# MC2.net
KiCad netlist of a schematic drawn in Altium Designer
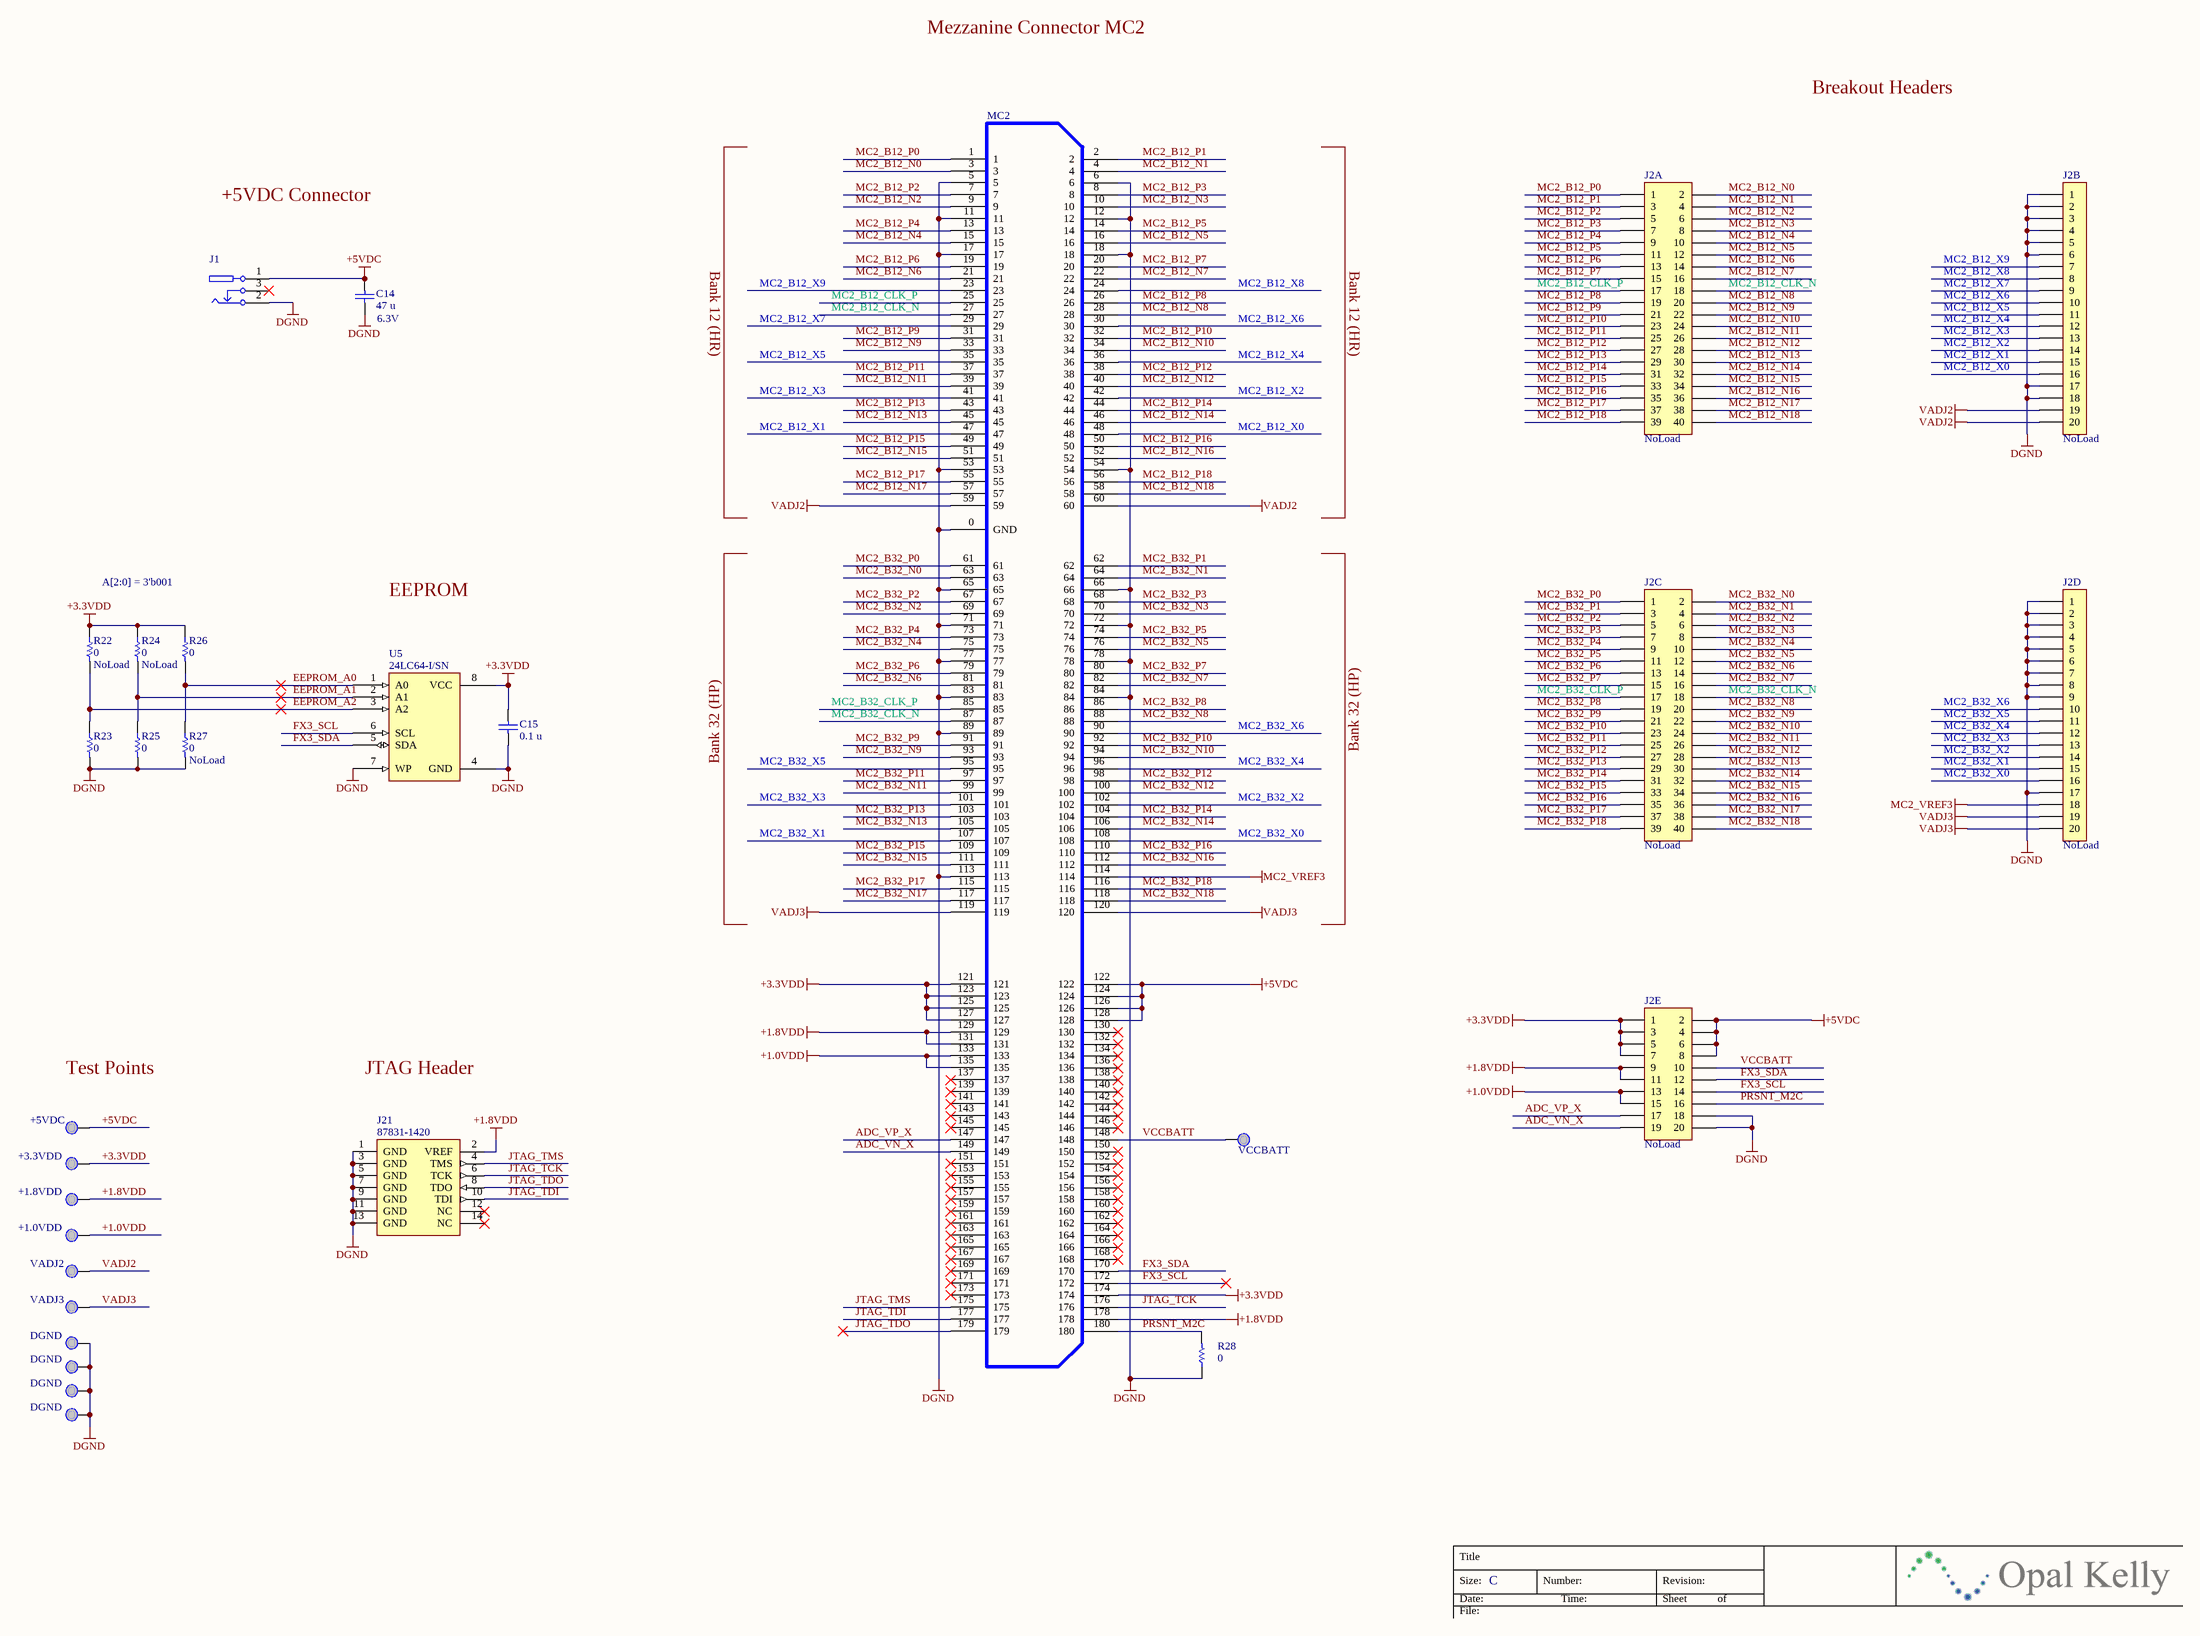
[diagram p0: MC2.SchDoc]

(export (version "E")
  (design (tool "Eeschema 10.0.6"))
  (components
    (comp (ref "C14")
      (value "47 u")
      (footprint "CAPC3216N")
      (description "Ceramic Capacitor")
      (fields
        (field (name "MANUFACTURER") "Taiyo Yuden")
        (field (name "PARTNUMBER") "000570")
        (field (name "VOLTAGERATING") "6.3V")
      )
      (libsource (lib "Aligni") (part "Capacitor"))
    )
    (comp (ref "C15")
      (value "0.1 u")
      (footprint "CAPC1005N")
      (description "Ceramic capacitor")
      (fields (field (name "MANUFACTURER") "Kemet") (field (name "PARTNUMBER") "000070"))
      (libsource (lib "Aligni") (part "Capacitor"))
    )
    (comp (ref "J1")
      (value "PJ-102AH")
      (footprint "CUI-PJ102A")
      (description "DC power connector - high current")
      (fields (field (name "MANUFACTURER") "CUI Inc.") (field (name "PARTNUMBER") "000356"))
      (libsource (lib "Aligni") (part "DCPOWER"))
    )
    (comp (ref "J2A")
      (value "0877584016")
      (footprint "HDR2X20-2MM")
      (description "2mm header, 20x2, thru-hole")
      (fields
        (field (name "MANUFACTURER") "Molex")
        (field (name "PARTNUMBER") "000583")
        (field (name "NOLOAD") "NoLoad")
      )
      (libsource (lib "Aligni") (part "Header 20X2"))
    )
    (comp (ref "J2B")
      (value "Header, 20-Pin, Single Row")
      (footprint "HDR1X20-2MM")
      (description "2mm header, 20x1, thru-hole")
      (fields
        (field (name "PARTNUMBER") "001334")
        (field (name "MANUFACTURER") "3M")
        (field (name "NOLOAD") "NoLoad")
      )
      (libsource (lib "Aligni") (part "Header 1X20"))
    )
    (comp (ref "J2C")
      (value "0877584016")
      (footprint "HDR2X20-2MM")
      (description "2mm header, 20x2, thru-hole")
      (fields
        (field (name "MANUFACTURER") "Molex")
        (field (name "PARTNUMBER") "000583")
        (field (name "NOLOAD") "NoLoad")
      )
      (libsource (lib "Aligni") (part "Header 20X2"))
    )
    (comp (ref "J2D")
      (value "Header, 20-Pin, Single Row")
      (footprint "HDR1X20-2MM")
      (description "2mm header, 20x1, thru-hole")
      (fields
        (field (name "PARTNUMBER") "001334")
        (field (name "MANUFACTURER") "3M")
        (field (name "NOLOAD") "NoLoad")
      )
      (libsource (lib "Aligni") (part "Header 1X20"))
    )
    (comp (ref "J2E")
      (value "0877582016")
      (footprint "HDR2X10-2MM")
      (description "2mm header, 10x2, thru-hole")
      (fields
        (field (name "MANUFACTURER") "Molex")
        (field (name "PARTNUMBER") "001338")
        (field (name "NOLOAD") "NoLoad")
      )
      (libsource (lib "Aligni") (part "Header 10X2"))
    )
    (comp (ref "J21")
      (value "87831-1420")
      (footprint "HDR2X7-2MM")
      (description "2mm header, shrouded")
      (fields (field (name "MANUFACTURER") "Molex") (field (name "PARTNUMBER") "000541"))
      (libsource (lib "Aligni") (part "JTAGXLNX"))
    )
    (comp (ref "MC2")
      (value "QTH-090-01-F-D-A")
      (footprint "QTH-090-01-X-D")
      (description "0.5mm hi-speed, high-density header (Female)")
      (fields (field (name "MANUFACTURER") "Samtec") (field (name "PARTNUMBER") "000876"))
      (libsource (lib "Aligni") (part "QTH-090"))
    )
    (comp (ref "R22")
      (value "0")
      (footprint "RESC1005N")
      (description "Thick-film resistor")
      (fields
        (field (name "MANUFACTURER") "Vishay")
        (field (name "PARTNUMBER") "000755")
        (field (name "NOLOAD") "NoLoad")
      )
      (libsource (lib "Aligni") (part "Resistor"))
    )
    (comp (ref "R23")
      (value "0")
      (footprint "RESC1005N")
      (description "Thick-film resistor")
      (fields (field (name "MANUFACTURER") "Vishay") (field (name "PARTNUMBER") "000755"))
      (libsource (lib "Aligni") (part "Resistor"))
    )
    (comp (ref "R24")
      (value "0")
      (footprint "RESC1005N")
      (description "Thick-film resistor")
      (fields
        (field (name "MANUFACTURER") "Vishay")
        (field (name "PARTNUMBER") "000755")
        (field (name "NOLOAD") "NoLoad")
      )
      (libsource (lib "Aligni") (part "Resistor"))
    )
    (comp (ref "R25")
      (value "0")
      (footprint "RESC1005N")
      (description "Thick-film resistor")
      (fields (field (name "MANUFACTURER") "Vishay") (field (name "PARTNUMBER") "000755"))
      (libsource (lib "Aligni") (part "Resistor"))
    )
    (comp (ref "R26")
      (value "0")
      (footprint "RESC1005N")
      (description "Thick-film resistor")
      (fields (field (name "MANUFACTURER") "Vishay") (field (name "PARTNUMBER") "000755"))
      (libsource (lib "Aligni") (part "Resistor"))
    )
    (comp (ref "R27")
      (value "0")
      (footprint "RESC1005N")
      (description "Thick-film resistor")
      (fields
        (field (name "MANUFACTURER") "Vishay")
        (field (name "PARTNUMBER") "000755")
        (field (name "NOLOAD") "NoLoad")
      )
      (libsource (lib "Aligni") (part "Resistor"))
    )
    (comp (ref "R28")
      (value "0")
      (footprint "RESC1608N")
      (description "Zero-ohm resistor")
      (fields (field (name "MANUFACTURER") "Vishay") (field (name "PARTNUMBER") "000411"))
      (libsource (lib "Aligni") (part "Resistor"))
    )
    (comp (ref "TP2")
      (value "+5VDC")
      (footprint "TP_MED")
      (description "Testpoint")
      (fields (field (name "MANUFACTURER") "Keystone Electronics") (field (name "PARTNUMBER") "000265"))
      (libsource (lib "Aligni") (part "TESTPOINT"))
    )
    (comp (ref "TP3")
      (value "+3.3VDD")
      (footprint "TP_MED")
      (description "Testpoint")
      (fields (field (name "MANUFACTURER") "Keystone Electronics") (field (name "PARTNUMBER") "000265"))
      (libsource (lib "Aligni") (part "TESTPOINT"))
    )
    (comp (ref "TP4")
      (value "+1.8VDD")
      (footprint "TP_MED")
      (description "Testpoint")
      (fields (field (name "MANUFACTURER") "Keystone Electronics") (field (name "PARTNUMBER") "000265"))
      (libsource (lib "Aligni") (part "TESTPOINT"))
    )
    (comp (ref "TP5")
      (value "+1.0VDD")
      (footprint "TP_MED")
      (description "Testpoint")
      (fields (field (name "MANUFACTURER") "Keystone Electronics") (field (name "PARTNUMBER") "000265"))
      (libsource (lib "Aligni") (part "TESTPOINT"))
    )
    (comp (ref "TP6")
      (value "VCCBATT")
      (footprint "TP_MED")
      (description "Testpoint")
      (fields (field (name "MANUFACTURER") "Keystone Electronics") (field (name "PARTNUMBER") "000265"))
      (libsource (lib "Aligni") (part "TESTPOINT"))
    )
    (comp (ref "TP9")
      (value "VADJ2")
      (footprint "TP_MED")
      (description "Testpoint")
      (fields (field (name "MANUFACTURER") "Keystone Electronics") (field (name "PARTNUMBER") "000265"))
      (libsource (lib "Aligni") (part "TESTPOINT"))
    )
    (comp (ref "TP10")
      (value "VADJ3")
      (footprint "TP_MED")
      (description "Testpoint")
      (fields (field (name "MANUFACTURER") "Keystone Electronics") (field (name "PARTNUMBER") "000265"))
      (libsource (lib "Aligni") (part "TESTPOINT"))
    )
    (comp (ref "TP11")
      (value "DGND")
      (footprint "TP_MED")
      (description "Testpoint")
      (fields (field (name "MANUFACTURER") "Keystone Electronics") (field (name "PARTNUMBER") "000265"))
      (libsource (lib "Aligni") (part "TESTPOINT"))
    )
    (comp (ref "TP12")
      (value "DGND")
      (footprint "TP_MED")
      (description "Testpoint")
      (fields (field (name "MANUFACTURER") "Keystone Electronics") (field (name "PARTNUMBER") "000265"))
      (libsource (lib "Aligni") (part "TESTPOINT"))
    )
    (comp (ref "TP13")
      (value "DGND")
      (footprint "TP_MED")
      (description "Testpoint")
      (fields (field (name "MANUFACTURER") "Keystone Electronics") (field (name "PARTNUMBER") "000265"))
      (libsource (lib "Aligni") (part "TESTPOINT"))
    )
    (comp (ref "TP14")
      (value "DGND")
      (footprint "TP_MED")
      (description "Testpoint")
      (fields (field (name "MANUFACTURER") "Keystone Electronics") (field (name "PARTNUMBER") "000265"))
      (libsource (lib "Aligni") (part "TESTPOINT"))
    )
    (comp (ref "U5")
      (value "24LC64-I/SN")
      (footprint "SO-G8")
      (description "EEPROM")
      (fields (field (name "MANUFACTURER") "Microchip") (field (name "PARTNUMBER") "000004"))
      (libsource (lib "Aligni") (part "24LCXX"))
    )
  )
  (nets
    (net (code "1") (name "+1.0VDD") (class "Default")
      (node (ref "J2E") (pin "13") (pinfunction "13_13") (pintype "passive"))
      (node (ref "J2E") (pin "15") (pinfunction "15_15") (pintype "passive"))
      (node (ref "MC2") (pin "133") (pinfunction "133_133") (pintype "passive"))
      (node (ref "MC2") (pin "135") (pinfunction "135_135") (pintype "passive"))
      (node (ref "TP5") (pin "1") (pinfunction "PIN_1") (pintype "passive"))
    )
    (net (code "2") (name "+1.8VDD") (class "Default")
      (node (ref "J21") (pin "2") (pinfunction "VREF_2") (pintype "power_in"))
      (node (ref "J2E") (pin "11") (pinfunction "11_11") (pintype "passive"))
      (node (ref "J2E") (pin "9") (pinfunction "9_9") (pintype "passive"))
      (node (ref "MC2") (pin "129") (pinfunction "129_129") (pintype "passive"))
      (node (ref "MC2") (pin "131") (pinfunction "131_131") (pintype "passive"))
      (node (ref "MC2") (pin "178") (pinfunction "178_178") (pintype "passive"))
      (node (ref "TP4") (pin "1") (pinfunction "PIN_1") (pintype "passive"))
    )
    (net (code "3") (name "+3.3VDD") (class "Default")
      (node (ref "C15") (pin "1") (pinfunction "1_1") (pintype "passive"))
      (node (ref "J2E") (pin "1") (pinfunction "1_1") (pintype "passive"))
      (node (ref "J2E") (pin "3") (pinfunction "3_3") (pintype "passive"))
      (node (ref "J2E") (pin "5") (pinfunction "5_5") (pintype "passive"))
      (node (ref "J2E") (pin "7") (pinfunction "7_7") (pintype "passive"))
      (node (ref "MC2") (pin "121") (pinfunction "121_121") (pintype "passive"))
      (node (ref "MC2") (pin "123") (pinfunction "123_123") (pintype "passive"))
      (node (ref "MC2") (pin "125") (pinfunction "125_125") (pintype "passive"))
      (node (ref "MC2") (pin "127") (pinfunction "127_127") (pintype "passive"))
      (node (ref "MC2") (pin "174") (pinfunction "174_174") (pintype "passive"))
      (node (ref "R22") (pin "1") (pinfunction "1_1") (pintype "passive"))
      (node (ref "R24") (pin "1") (pinfunction "1_1") (pintype "passive"))
      (node (ref "R26") (pin "1") (pinfunction "1_1") (pintype "passive"))
      (node (ref "TP3") (pin "1") (pinfunction "PIN_1") (pintype "passive"))
      (node (ref "U5") (pin "8") (pinfunction "VCC_8") (pintype "power_in"))
    )
    (net (code "4") (name "+5VDC") (class "Default")
      (node (ref "C14") (pin "1") (pinfunction "1_1") (pintype "passive"))
      (node (ref "J1") (pin "1") (pinfunction "1_1") (pintype "passive"))
      (node (ref "J2E") (pin "2") (pinfunction "2_2") (pintype "passive"))
      (node (ref "J2E") (pin "4") (pinfunction "4_4") (pintype "passive"))
      (node (ref "J2E") (pin "6") (pinfunction "6_6") (pintype "passive"))
      (node (ref "J2E") (pin "8") (pinfunction "8_8") (pintype "passive"))
      (node (ref "MC2") (pin "122") (pinfunction "122_122") (pintype "passive"))
      (node (ref "MC2") (pin "124") (pinfunction "124_124") (pintype "passive"))
      (node (ref "MC2") (pin "126") (pinfunction "126_126") (pintype "passive"))
      (node (ref "MC2") (pin "128") (pinfunction "128_128") (pintype "passive"))
      (node (ref "TP2") (pin "1") (pinfunction "PIN_1") (pintype "passive"))
    )
    (net (code "5") (name "/ADC_VN_X") (class "Default")
      (node (ref "J2E") (pin "19") (pinfunction "19_19") (pintype "passive"))
      (node (ref "MC2") (pin "149") (pinfunction "149_149") (pintype "passive"))
    )
    (net (code "6") (name "/ADC_VP_X") (class "Default")
      (node (ref "J2E") (pin "17") (pinfunction "17_17") (pintype "passive"))
      (node (ref "MC2") (pin "147") (pinfunction "147_147") (pintype "passive"))
    )
    (net (code "7") (name "/EEPROM_A0") (class "Default")
      (node (ref "R26") (pin "2") (pinfunction "2_2") (pintype "passive"))
      (node (ref "R27") (pin "1") (pinfunction "1_1") (pintype "passive"))
      (node (ref "U5") (pin "1") (pinfunction "A0_1") (pintype "input"))
    )
    (net (code "8") (name "/EEPROM_A1") (class "Default")
      (node (ref "R24") (pin "2") (pinfunction "2_2") (pintype "passive"))
      (node (ref "R25") (pin "1") (pinfunction "1_1") (pintype "passive"))
      (node (ref "U5") (pin "2") (pinfunction "A1_2") (pintype "input"))
    )
    (net (code "9") (name "/EEPROM_A2") (class "Default")
      (node (ref "R22") (pin "2") (pinfunction "2_2") (pintype "passive"))
      (node (ref "R23") (pin "1") (pinfunction "1_1") (pintype "passive"))
      (node (ref "U5") (pin "3") (pinfunction "A2_3") (pintype "input"))
    )
    (net (code "10") (name "/FX3_SCL") (class "Default")
      (node (ref "J2E") (pin "14") (pinfunction "14_14") (pintype "passive"))
      (node (ref "MC2") (pin "172") (pinfunction "172_172") (pintype "passive"))
      (node (ref "U5") (pin "6") (pinfunction "SCL_6") (pintype "input"))
    )
    (net (code "11") (name "/FX3_SDA") (class "Default")
      (node (ref "J2E") (pin "12") (pinfunction "12_12") (pintype "passive"))
      (node (ref "MC2") (pin "170") (pinfunction "170_170") (pintype "passive"))
      (node (ref "U5") (pin "5") (pinfunction "SDA_5") (pintype "bidirectional"))
    )
    (net (code "12") (name "/JTAG_TCK") (class "Default")
      (node (ref "J21") (pin "6") (pinfunction "TCK_6") (pintype "output"))
      (node (ref "MC2") (pin "176") (pinfunction "176_176") (pintype "passive"))
    )
    (net (code "13") (name "/JTAG_TDI") (class "Default")
      (node (ref "J21") (pin "10") (pinfunction "TDI_10") (pintype "output"))
      (node (ref "MC2") (pin "177") (pinfunction "177_177") (pintype "passive"))
    )
    (net (code "14") (name "/JTAG_TDO") (class "Default")
      (node (ref "J21") (pin "8") (pinfunction "TDO_8") (pintype "input"))
      (node (ref "MC2") (pin "179") (pinfunction "179_179") (pintype "passive"))
    )
    (net (code "15") (name "/JTAG_TMS") (class "Default")
      (node (ref "J21") (pin "4") (pinfunction "TMS_4") (pintype "output"))
      (node (ref "MC2") (pin "175") (pinfunction "175_175") (pintype "passive"))
    )
    (net (code "16") (name "/MC2_B12_CLK_N") (class "Default")
      (node (ref "J2A") (pin "18") (pinfunction "18_18") (pintype "passive"))
      (node (ref "MC2") (pin "27") (pinfunction "27_27") (pintype "passive"))
    )
    (net (code "17") (name "/MC2_B12_CLK_P") (class "Default")
      (node (ref "J2A") (pin "17") (pinfunction "17_17") (pintype "passive"))
      (node (ref "MC2") (pin "25") (pinfunction "25_25") (pintype "passive"))
    )
    (net (code "18") (name "/MC2_B12_N0") (class "Default")
      (node (ref "J2A") (pin "2") (pinfunction "2_2") (pintype "passive"))
      (node (ref "MC2") (pin "3") (pinfunction "3_3") (pintype "passive"))
    )
    (net (code "19") (name "/MC2_B12_N1") (class "Default")
      (node (ref "J2A") (pin "4") (pinfunction "4_4") (pintype "passive"))
      (node (ref "MC2") (pin "4") (pinfunction "4_4") (pintype "passive"))
    )
    (net (code "20") (name "/MC2_B12_N2") (class "Default")
      (node (ref "J2A") (pin "6") (pinfunction "6_6") (pintype "passive"))
      (node (ref "MC2") (pin "9") (pinfunction "9_9") (pintype "passive"))
    )
    (net (code "21") (name "/MC2_B12_N3") (class "Default")
      (node (ref "J2A") (pin "8") (pinfunction "8_8") (pintype "passive"))
      (node (ref "MC2") (pin "10") (pinfunction "10_10") (pintype "passive"))
    )
    (net (code "22") (name "/MC2_B12_N4") (class "Default")
      (node (ref "J2A") (pin "10") (pinfunction "10_10") (pintype "passive"))
      (node (ref "MC2") (pin "15") (pinfunction "15_15") (pintype "passive"))
    )
    (net (code "23") (name "/MC2_B12_N5") (class "Default")
      (node (ref "J2A") (pin "12") (pinfunction "12_12") (pintype "passive"))
      (node (ref "MC2") (pin "16") (pinfunction "16_16") (pintype "passive"))
    )
    (net (code "24") (name "/MC2_B12_N6") (class "Default")
      (node (ref "J2A") (pin "14") (pinfunction "14_14") (pintype "passive"))
      (node (ref "MC2") (pin "21") (pinfunction "21_21") (pintype "passive"))
    )
    (net (code "25") (name "/MC2_B12_N7") (class "Default")
      (node (ref "J2A") (pin "16") (pinfunction "16_16") (pintype "passive"))
      (node (ref "MC2") (pin "22") (pinfunction "22_22") (pintype "passive"))
    )
    (net (code "26") (name "/MC2_B12_N8") (class "Default")
      (node (ref "J2A") (pin "20") (pinfunction "20_20") (pintype "passive"))
      (node (ref "MC2") (pin "28") (pinfunction "28_28") (pintype "passive"))
    )
    (net (code "27") (name "/MC2_B12_N9") (class "Default")
      (node (ref "J2A") (pin "22") (pinfunction "22_22") (pintype "passive"))
      (node (ref "MC2") (pin "33") (pinfunction "33_33") (pintype "passive"))
    )
    (net (code "28") (name "/MC2_B12_N10") (class "Default")
      (node (ref "J2A") (pin "24") (pinfunction "24_24") (pintype "passive"))
      (node (ref "MC2") (pin "34") (pinfunction "34_34") (pintype "passive"))
    )
    (net (code "29") (name "/MC2_B12_N11") (class "Default")
      (node (ref "J2A") (pin "26") (pinfunction "26_26") (pintype "passive"))
      (node (ref "MC2") (pin "39") (pinfunction "39_39") (pintype "passive"))
    )
    (net (code "30") (name "/MC2_B12_N12") (class "Default")
      (node (ref "J2A") (pin "28") (pinfunction "28_28") (pintype "passive"))
      (node (ref "MC2") (pin "40") (pinfunction "40_40") (pintype "passive"))
    )
    (net (code "31") (name "/MC2_B12_N13") (class "Default")
      (node (ref "J2A") (pin "30") (pinfunction "30_30") (pintype "passive"))
      (node (ref "MC2") (pin "45") (pinfunction "45_45") (pintype "passive"))
    )
    (net (code "32") (name "/MC2_B12_N14") (class "Default")
      (node (ref "J2A") (pin "32") (pinfunction "32_32") (pintype "passive"))
      (node (ref "MC2") (pin "46") (pinfunction "46_46") (pintype "passive"))
    )
    (net (code "33") (name "/MC2_B12_N15") (class "Default")
      (node (ref "J2A") (pin "34") (pinfunction "34_34") (pintype "passive"))
      (node (ref "MC2") (pin "51") (pinfunction "51_51") (pintype "passive"))
    )
    (net (code "34") (name "/MC2_B12_N16") (class "Default")
      (node (ref "J2A") (pin "36") (pinfunction "36_36") (pintype "passive"))
      (node (ref "MC2") (pin "52") (pinfunction "52_52") (pintype "passive"))
    )
    (net (code "35") (name "/MC2_B12_N17") (class "Default")
      (node (ref "J2A") (pin "38") (pinfunction "38_38") (pintype "passive"))
      (node (ref "MC2") (pin "57") (pinfunction "57_57") (pintype "passive"))
    )
    (net (code "36") (name "/MC2_B12_N18") (class "Default")
      (node (ref "J2A") (pin "40") (pinfunction "40_40") (pintype "passive"))
      (node (ref "MC2") (pin "58") (pinfunction "58_58") (pintype "passive"))
    )
    (net (code "37") (name "/MC2_B12_P0") (class "Default")
      (node (ref "J2A") (pin "1") (pinfunction "1_1") (pintype "passive"))
      (node (ref "MC2") (pin "1") (pinfunction "1_1") (pintype "passive"))
    )
    (net (code "38") (name "/MC2_B12_P1") (class "Default")
      (node (ref "J2A") (pin "3") (pinfunction "3_3") (pintype "passive"))
      (node (ref "MC2") (pin "2") (pinfunction "2_2") (pintype "passive"))
    )
    (net (code "39") (name "/MC2_B12_P2") (class "Default")
      (node (ref "J2A") (pin "5") (pinfunction "5_5") (pintype "passive"))
      (node (ref "MC2") (pin "7") (pinfunction "7_7") (pintype "passive"))
    )
    (net (code "40") (name "/MC2_B12_P3") (class "Default")
      (node (ref "J2A") (pin "7") (pinfunction "7_7") (pintype "passive"))
      (node (ref "MC2") (pin "8") (pinfunction "8_8") (pintype "passive"))
    )
    (net (code "41") (name "/MC2_B12_P4") (class "Default")
      (node (ref "J2A") (pin "9") (pinfunction "9_9") (pintype "passive"))
      (node (ref "MC2") (pin "13") (pinfunction "13_13") (pintype "passive"))
    )
    (net (code "42") (name "/MC2_B12_P5") (class "Default")
      (node (ref "J2A") (pin "11") (pinfunction "11_11") (pintype "passive"))
      (node (ref "MC2") (pin "14") (pinfunction "14_14") (pintype "passive"))
    )
    (net (code "43") (name "/MC2_B12_P6") (class "Default")
      (node (ref "J2A") (pin "13") (pinfunction "13_13") (pintype "passive"))
      (node (ref "MC2") (pin "19") (pinfunction "19_19") (pintype "passive"))
    )
    (net (code "44") (name "/MC2_B12_P7") (class "Default")
      (node (ref "J2A") (pin "15") (pinfunction "15_15") (pintype "passive"))
      (node (ref "MC2") (pin "20") (pinfunction "20_20") (pintype "passive"))
    )
    (net (code "45") (name "/MC2_B12_P8") (class "Default")
      (node (ref "J2A") (pin "19") (pinfunction "19_19") (pintype "passive"))
      (node (ref "MC2") (pin "26") (pinfunction "26_26") (pintype "passive"))
    )
    (net (code "46") (name "/MC2_B12_P9") (class "Default")
      (node (ref "J2A") (pin "21") (pinfunction "21_21") (pintype "passive"))
      (node (ref "MC2") (pin "31") (pinfunction "31_31") (pintype "passive"))
    )
    (net (code "47") (name "/MC2_B12_P10") (class "Default")
      (node (ref "J2A") (pin "23") (pinfunction "23_23") (pintype "passive"))
      (node (ref "MC2") (pin "32") (pinfunction "32_32") (pintype "passive"))
    )
    (net (code "48") (name "/MC2_B12_P11") (class "Default")
      (node (ref "J2A") (pin "25") (pinfunction "25_25") (pintype "passive"))
      (node (ref "MC2") (pin "37") (pinfunction "37_37") (pintype "passive"))
    )
    (net (code "49") (name "/MC2_B12_P12") (class "Default")
      (node (ref "J2A") (pin "27") (pinfunction "27_27") (pintype "passive"))
      (node (ref "MC2") (pin "38") (pinfunction "38_38") (pintype "passive"))
    )
    (net (code "50") (name "/MC2_B12_P13") (class "Default")
      (node (ref "J2A") (pin "29") (pinfunction "29_29") (pintype "passive"))
      (node (ref "MC2") (pin "43") (pinfunction "43_43") (pintype "passive"))
    )
    (net (code "51") (name "/MC2_B12_P14") (class "Default")
      (node (ref "J2A") (pin "31") (pinfunction "31_31") (pintype "passive"))
      (node (ref "MC2") (pin "44") (pinfunction "44_44") (pintype "passive"))
    )
    (net (code "52") (name "/MC2_B12_P15") (class "Default")
      (node (ref "J2A") (pin "33") (pinfunction "33_33") (pintype "passive"))
      (node (ref "MC2") (pin "49") (pinfunction "49_49") (pintype "passive"))
    )
    (net (code "53") (name "/MC2_B12_P16") (class "Default")
      (node (ref "J2A") (pin "35") (pinfunction "35_35") (pintype "passive"))
      (node (ref "MC2") (pin "50") (pinfunction "50_50") (pintype "passive"))
    )
    (net (code "54") (name "/MC2_B12_P17") (class "Default")
      (node (ref "J2A") (pin "37") (pinfunction "37_37") (pintype "passive"))
      (node (ref "MC2") (pin "55") (pinfunction "55_55") (pintype "passive"))
    )
    (net (code "55") (name "/MC2_B12_P18") (class "Default")
      (node (ref "J2A") (pin "39") (pinfunction "39_39") (pintype "passive"))
      (node (ref "MC2") (pin "56") (pinfunction "56_56") (pintype "passive"))
    )
    (net (code "56") (name "/MC2_B12_X0") (class "Default")
      (node (ref "J2B") (pin "16") (pinfunction "16_16") (pintype "passive"))
      (node (ref "MC2") (pin "48") (pinfunction "48_48") (pintype "passive"))
    )
    (net (code "57") (name "/MC2_B12_X1") (class "Default")
      (node (ref "J2B") (pin "15") (pinfunction "15_15") (pintype "passive"))
      (node (ref "MC2") (pin "47") (pinfunction "47_47") (pintype "passive"))
    )
    (net (code "58") (name "/MC2_B12_X2") (class "Default")
      (node (ref "J2B") (pin "14") (pinfunction "14_14") (pintype "passive"))
      (node (ref "MC2") (pin "42") (pinfunction "42_42") (pintype "passive"))
    )
    (net (code "59") (name "/MC2_B12_X3") (class "Default")
      (node (ref "J2B") (pin "13") (pinfunction "13_13") (pintype "passive"))
      (node (ref "MC2") (pin "41") (pinfunction "41_41") (pintype "passive"))
    )
    (net (code "60") (name "/MC2_B12_X4") (class "Default")
      (node (ref "J2B") (pin "12") (pinfunction "12_12") (pintype "passive"))
      (node (ref "MC2") (pin "36") (pinfunction "36_36") (pintype "passive"))
    )
    (net (code "61") (name "/MC2_B12_X5") (class "Default")
      (node (ref "J2B") (pin "11") (pinfunction "11_11") (pintype "passive"))
      (node (ref "MC2") (pin "35") (pinfunction "35_35") (pintype "passive"))
    )
    (net (code "62") (name "/MC2_B12_X6") (class "Default")
      (node (ref "J2B") (pin "10") (pinfunction "10_10") (pintype "passive"))
      (node (ref "MC2") (pin "30") (pinfunction "30_30") (pintype "passive"))
    )
    (net (code "63") (name "/MC2_B12_X7") (class "Default")
      (node (ref "J2B") (pin "9") (pinfunction "9_9") (pintype "passive"))
      (node (ref "MC2") (pin "29") (pinfunction "29_29") (pintype "passive"))
    )
    (net (code "64") (name "/MC2_B12_X8") (class "Default")
      (node (ref "J2B") (pin "8") (pinfunction "8_8") (pintype "passive"))
      (node (ref "MC2") (pin "24") (pinfunction "24_24") (pintype "passive"))
    )
    (net (code "65") (name "/MC2_B12_X9") (class "Default")
      (node (ref "J2B") (pin "7") (pinfunction "7_7") (pintype "passive"))
      (node (ref "MC2") (pin "23") (pinfunction "23_23") (pintype "passive"))
    )
    (net (code "66") (name "/MC2_B32_CLK_N") (class "Default")
      (node (ref "J2C") (pin "18") (pinfunction "18_18") (pintype "passive"))
      (node (ref "MC2") (pin "87") (pinfunction "87_87") (pintype "passive"))
    )
    (net (code "67") (name "/MC2_B32_CLK_P") (class "Default")
      (node (ref "J2C") (pin "17") (pinfunction "17_17") (pintype "passive"))
      (node (ref "MC2") (pin "85") (pinfunction "85_85") (pintype "passive"))
    )
    (net (code "68") (name "/MC2_B32_N0") (class "Default")
      (node (ref "J2C") (pin "2") (pinfunction "2_2") (pintype "passive"))
      (node (ref "MC2") (pin "63") (pinfunction "63_63") (pintype "passive"))
    )
    (net (code "69") (name "/MC2_B32_N1") (class "Default")
      (node (ref "J2C") (pin "4") (pinfunction "4_4") (pintype "passive"))
      (node (ref "MC2") (pin "64") (pinfunction "64_64") (pintype "passive"))
    )
    (net (code "70") (name "/MC2_B32_N2") (class "Default")
      (node (ref "J2C") (pin "6") (pinfunction "6_6") (pintype "passive"))
      (node (ref "MC2") (pin "69") (pinfunction "69_69") (pintype "passive"))
    )
    (net (code "71") (name "/MC2_B32_N3") (class "Default")
      (node (ref "J2C") (pin "8") (pinfunction "8_8") (pintype "passive"))
      (node (ref "MC2") (pin "70") (pinfunction "70_70") (pintype "passive"))
    )
    (net (code "72") (name "/MC2_B32_N4") (class "Default")
      (node (ref "J2C") (pin "10") (pinfunction "10_10") (pintype "passive"))
      (node (ref "MC2") (pin "75") (pinfunction "75_75") (pintype "passive"))
    )
    (net (code "73") (name "/MC2_B32_N5") (class "Default")
      (node (ref "J2C") (pin "12") (pinfunction "12_12") (pintype "passive"))
      (node (ref "MC2") (pin "76") (pinfunction "76_76") (pintype "passive"))
    )
    (net (code "74") (name "/MC2_B32_N6") (class "Default")
      (node (ref "J2C") (pin "14") (pinfunction "14_14") (pintype "passive"))
      (node (ref "MC2") (pin "81") (pinfunction "81_81") (pintype "passive"))
    )
    (net (code "75") (name "/MC2_B32_N7") (class "Default")
      (node (ref "J2C") (pin "16") (pinfunction "16_16") (pintype "passive"))
      (node (ref "MC2") (pin "82") (pinfunction "82_82") (pintype "passive"))
    )
    (net (code "76") (name "/MC2_B32_N8") (class "Default")
      (node (ref "J2C") (pin "20") (pinfunction "20_20") (pintype "passive"))
      (node (ref "MC2") (pin "88") (pinfunction "88_88") (pintype "passive"))
    )
    (net (code "77") (name "/MC2_B32_N9") (class "Default")
      (node (ref "J2C") (pin "22") (pinfunction "22_22") (pintype "passive"))
      (node (ref "MC2") (pin "93") (pinfunction "93_93") (pintype "passive"))
    )
    (net (code "78") (name "/MC2_B32_N10") (class "Default")
      (node (ref "J2C") (pin "24") (pinfunction "24_24") (pintype "passive"))
      (node (ref "MC2") (pin "94") (pinfunction "94_94") (pintype "passive"))
    )
    (net (code "79") (name "/MC2_B32_N11") (class "Default")
      (node (ref "J2C") (pin "26") (pinfunction "26_26") (pintype "passive"))
      (node (ref "MC2") (pin "99") (pinfunction "99_99") (pintype "passive"))
    )
    (net (code "80") (name "/MC2_B32_N12") (class "Default")
      (node (ref "J2C") (pin "28") (pinfunction "28_28") (pintype "passive"))
      (node (ref "MC2") (pin "100") (pinfunction "100_100") (pintype "passive"))
    )
    (net (code "81") (name "/MC2_B32_N13") (class "Default")
      (node (ref "J2C") (pin "30") (pinfunction "30_30") (pintype "passive"))
      (node (ref "MC2") (pin "105") (pinfunction "105_105") (pintype "passive"))
    )
    (net (code "82") (name "/MC2_B32_N14") (class "Default")
      (node (ref "J2C") (pin "32") (pinfunction "32_32") (pintype "passive"))
      (node (ref "MC2") (pin "106") (pinfunction "106_106") (pintype "passive"))
    )
    (net (code "83") (name "/MC2_B32_N15") (class "Default")
      (node (ref "J2C") (pin "34") (pinfunction "34_34") (pintype "passive"))
      (node (ref "MC2") (pin "111") (pinfunction "111_111") (pintype "passive"))
    )
    (net (code "84") (name "/MC2_B32_N16") (class "Default")
      (node (ref "J2C") (pin "36") (pinfunction "36_36") (pintype "passive"))
      (node (ref "MC2") (pin "112") (pinfunction "112_112") (pintype "passive"))
    )
    (net (code "85") (name "/MC2_B32_N17") (class "Default")
      (node (ref "J2C") (pin "38") (pinfunction "38_38") (pintype "passive"))
      (node (ref "MC2") (pin "117") (pinfunction "117_117") (pintype "passive"))
    )
    (net (code "86") (name "/MC2_B32_N18") (class "Default")
      (node (ref "J2C") (pin "40") (pinfunction "40_40") (pintype "passive"))
      (node (ref "MC2") (pin "118") (pinfunction "118_118") (pintype "passive"))
    )
    (net (code "87") (name "/MC2_B32_P0") (class "Default")
      (node (ref "J2C") (pin "1") (pinfunction "1_1") (pintype "passive"))
      (node (ref "MC2") (pin "61") (pinfunction "61_61") (pintype "passive"))
    )
    (net (code "88") (name "/MC2_B32_P1") (class "Default")
      (node (ref "J2C") (pin "3") (pinfunction "3_3") (pintype "passive"))
      (node (ref "MC2") (pin "62") (pinfunction "62_62") (pintype "passive"))
    )
    (net (code "89") (name "/MC2_B32_P2") (class "Default")
      (node (ref "J2C") (pin "5") (pinfunction "5_5") (pintype "passive"))
      (node (ref "MC2") (pin "67") (pinfunction "67_67") (pintype "passive"))
    )
    (net (code "90") (name "/MC2_B32_P3") (class "Default")
      (node (ref "J2C") (pin "7") (pinfunction "7_7") (pintype "passive"))
      (node (ref "MC2") (pin "68") (pinfunction "68_68") (pintype "passive"))
    )
    (net (code "91") (name "/MC2_B32_P4") (class "Default")
      (node (ref "J2C") (pin "9") (pinfunction "9_9") (pintype "passive"))
      (node (ref "MC2") (pin "73") (pinfunction "73_73") (pintype "passive"))
    )
    (net (code "92") (name "/MC2_B32_P5") (class "Default")
      (node (ref "J2C") (pin "11") (pinfunction "11_11") (pintype "passive"))
      (node (ref "MC2") (pin "74") (pinfunction "74_74") (pintype "passive"))
    )
    (net (code "93") (name "/MC2_B32_P6") (class "Default")
      (node (ref "J2C") (pin "13") (pinfunction "13_13") (pintype "passive"))
      (node (ref "MC2") (pin "79") (pinfunction "79_79") (pintype "passive"))
    )
    (net (code "94") (name "/MC2_B32_P7") (class "Default")
      (node (ref "J2C") (pin "15") (pinfunction "15_15") (pintype "passive"))
      (node (ref "MC2") (pin "80") (pinfunction "80_80") (pintype "passive"))
    )
    (net (code "95") (name "/MC2_B32_P8") (class "Default")
      (node (ref "J2C") (pin "19") (pinfunction "19_19") (pintype "passive"))
      (node (ref "MC2") (pin "86") (pinfunction "86_86") (pintype "passive"))
    )
    (net (code "96") (name "/MC2_B32_P9") (class "Default")
      (node (ref "J2C") (pin "21") (pinfunction "21_21") (pintype "passive"))
      (node (ref "MC2") (pin "91") (pinfunction "91_91") (pintype "passive"))
    )
    (net (code "97") (name "/MC2_B32_P10") (class "Default")
      (node (ref "J2C") (pin "23") (pinfunction "23_23") (pintype "passive"))
      (node (ref "MC2") (pin "92") (pinfunction "92_92") (pintype "passive"))
    )
    (net (code "98") (name "/MC2_B32_P11") (class "Default")
      (node (ref "J2C") (pin "25") (pinfunction "25_25") (pintype "passive"))
      (node (ref "MC2") (pin "97") (pinfunction "97_97") (pintype "passive"))
    )
    (net (code "99") (name "/MC2_B32_P12") (class "Default")
      (node (ref "J2C") (pin "27") (pinfunction "27_27") (pintype "passive"))
      (node (ref "MC2") (pin "98") (pinfunction "98_98") (pintype "passive"))
    )
    (net (code "100") (name "/MC2_B32_P13") (class "Default")
      (node (ref "J2C") (pin "29") (pinfunction "29_29") (pintype "passive"))
      (node (ref "MC2") (pin "103") (pinfunction "103_103") (pintype "passive"))
    )
    (net (code "101") (name "/MC2_B32_P14") (class "Default")
      (node (ref "J2C") (pin "31") (pinfunction "31_31") (pintype "passive"))
      (node (ref "MC2") (pin "104") (pinfunction "104_104") (pintype "passive"))
    )
    (net (code "102") (name "/MC2_B32_P15") (class "Default")
      (node (ref "J2C") (pin "33") (pinfunction "33_33") (pintype "passive"))
      (node (ref "MC2") (pin "109") (pinfunction "109_109") (pintype "passive"))
    )
    (net (code "103") (name "/MC2_B32_P16") (class "Default")
      (node (ref "J2C") (pin "35") (pinfunction "35_35") (pintype "passive"))
      (node (ref "MC2") (pin "110") (pinfunction "110_110") (pintype "passive"))
    )
    (net (code "104") (name "/MC2_B32_P17") (class "Default")
      (node (ref "J2C") (pin "37") (pinfunction "37_37") (pintype "passive"))
      (node (ref "MC2") (pin "115") (pinfunction "115_115") (pintype "passive"))
    )
    (net (code "105") (name "/MC2_B32_P18") (class "Default")
      (node (ref "J2C") (pin "39") (pinfunction "39_39") (pintype "passive"))
      (node (ref "MC2") (pin "116") (pinfunction "116_116") (pintype "passive"))
    )
    (net (code "106") (name "/MC2_B32_X0") (class "Default")
      (node (ref "J2D") (pin "16") (pinfunction "16_16") (pintype "passive"))
      (node (ref "MC2") (pin "108") (pinfunction "108_108") (pintype "passive"))
    )
    (net (code "107") (name "/MC2_B32_X1") (class "Default")
      (node (ref "J2D") (pin "15") (pinfunction "15_15") (pintype "passive"))
      (node (ref "MC2") (pin "107") (pinfunction "107_107") (pintype "passive"))
    )
    (net (code "108") (name "/MC2_B32_X2") (class "Default")
      (node (ref "J2D") (pin "14") (pinfunction "14_14") (pintype "passive"))
      (node (ref "MC2") (pin "102") (pinfunction "102_102") (pintype "passive"))
    )
    (net (code "109") (name "/MC2_B32_X3") (class "Default")
      (node (ref "J2D") (pin "13") (pinfunction "13_13") (pintype "passive"))
      (node (ref "MC2") (pin "101") (pinfunction "101_101") (pintype "passive"))
    )
    (net (code "110") (name "/MC2_B32_X4") (class "Default")
      (node (ref "J2D") (pin "12") (pinfunction "12_12") (pintype "passive"))
      (node (ref "MC2") (pin "96") (pinfunction "96_96") (pintype "passive"))
    )
    (net (code "111") (name "/MC2_B32_X5") (class "Default")
      (node (ref "J2D") (pin "11") (pinfunction "11_11") (pintype "passive"))
      (node (ref "MC2") (pin "95") (pinfunction "95_95") (pintype "passive"))
    )
    (net (code "112") (name "/MC2_B32_X6") (class "Default")
      (node (ref "J2D") (pin "10") (pinfunction "10_10") (pintype "passive"))
      (node (ref "MC2") (pin "90") (pinfunction "90_90") (pintype "passive"))
    )
    (net (code "113") (name "/PRSNT_M2C") (class "Default")
      (node (ref "J2E") (pin "16") (pinfunction "16_16") (pintype "passive"))
      (node (ref "MC2") (pin "180") (pinfunction "180_180") (pintype "passive"))
      (node (ref "R28") (pin "2") (pinfunction "2_2") (pintype "passive"))
    )
    (net (code "114") (name "/VCCBATT") (class "Default")
      (node (ref "J2E") (pin "10") (pinfunction "10_10") (pintype "passive"))
      (node (ref "MC2") (pin "148") (pinfunction "148_148") (pintype "passive"))
      (node (ref "TP6") (pin "1") (pinfunction "PIN_1") (pintype "passive"))
    )
    (net (code "115") (name "DGND") (class "Default")
      (node (ref "C14") (pin "2") (pinfunction "2_2") (pintype "passive"))
      (node (ref "C15") (pin "2") (pinfunction "2_2") (pintype "passive"))
      (node (ref "J1") (pin "2") (pinfunction "2_2") (pintype "passive"))
      (node (ref "J21") (pin "1") (pinfunction "GND_1") (pintype "power_in"))
      (node (ref "J21") (pin "11") (pinfunction "GND_11") (pintype "power_in"))
      (node (ref "J21") (pin "13") (pinfunction "GND_13") (pintype "power_in"))
      (node (ref "J21") (pin "3") (pinfunction "GND_3") (pintype "power_in"))
      (node (ref "J21") (pin "5") (pinfunction "GND_5") (pintype "power_in"))
      (node (ref "J21") (pin "7") (pinfunction "GND_7") (pintype "power_in"))
      (node (ref "J21") (pin "9") (pinfunction "GND_9") (pintype "power_in"))
      (node (ref "J2B") (pin "1") (pinfunction "1_1") (pintype "passive"))
      (node (ref "J2B") (pin "17") (pinfunction "17_17") (pintype "passive"))
      (node (ref "J2B") (pin "18") (pinfunction "18_18") (pintype "passive"))
      (node (ref "J2B") (pin "2") (pinfunction "2_2") (pintype "passive"))
      (node (ref "J2B") (pin "3") (pinfunction "3_3") (pintype "passive"))
      (node (ref "J2B") (pin "4") (pinfunction "4_4") (pintype "passive"))
      (node (ref "J2B") (pin "5") (pinfunction "5_5") (pintype "passive"))
      (node (ref "J2B") (pin "6") (pinfunction "6_6") (pintype "passive"))
      (node (ref "J2D") (pin "1") (pinfunction "1_1") (pintype "passive"))
      (node (ref "J2D") (pin "17") (pinfunction "17_17") (pintype "passive"))
      (node (ref "J2D") (pin "2") (pinfunction "2_2") (pintype "passive"))
      (node (ref "J2D") (pin "3") (pinfunction "3_3") (pintype "passive"))
      (node (ref "J2D") (pin "4") (pinfunction "4_4") (pintype "passive"))
      (node (ref "J2D") (pin "5") (pinfunction "5_5") (pintype "passive"))
      (node (ref "J2D") (pin "6") (pinfunction "6_6") (pintype "passive"))
      (node (ref "J2D") (pin "7") (pinfunction "7_7") (pintype "passive"))
      (node (ref "J2D") (pin "8") (pinfunction "8_8") (pintype "passive"))
      (node (ref "J2D") (pin "9") (pinfunction "9_9") (pintype "passive"))
      (node (ref "J2E") (pin "18") (pinfunction "18_18") (pintype "passive"))
      (node (ref "J2E") (pin "20") (pinfunction "20_20") (pintype "passive"))
      (node (ref "MC2") (pin "0") (pinfunction "GND_0") (pintype "power_in"))
      (node (ref "MC2") (pin "11") (pinfunction "11_11") (pintype "passive"))
      (node (ref "MC2") (pin "113") (pinfunction "113_113") (pintype "passive"))
      (node (ref "MC2") (pin "12") (pinfunction "12_12") (pintype "passive"))
      (node (ref "MC2") (pin "17") (pinfunction "17_17") (pintype "passive"))
      (node (ref "MC2") (pin "18") (pinfunction "18_18") (pintype "passive"))
      (node (ref "MC2") (pin "5") (pinfunction "5_5") (pintype "passive"))
      (node (ref "MC2") (pin "53") (pinfunction "53_53") (pintype "passive"))
      (node (ref "MC2") (pin "54") (pinfunction "54_54") (pintype "passive"))
      (node (ref "MC2") (pin "6") (pinfunction "6_6") (pintype "passive"))
      (node (ref "MC2") (pin "65") (pinfunction "65_65") (pintype "passive"))
      (node (ref "MC2") (pin "66") (pinfunction "66_66") (pintype "passive"))
      (node (ref "MC2") (pin "71") (pinfunction "71_71") (pintype "passive"))
      (node (ref "MC2") (pin "72") (pinfunction "72_72") (pintype "passive"))
      (node (ref "MC2") (pin "77") (pinfunction "77_77") (pintype "passive"))
      (node (ref "MC2") (pin "78") (pinfunction "78_78") (pintype "passive"))
      (node (ref "MC2") (pin "83") (pinfunction "83_83") (pintype "passive"))
      (node (ref "MC2") (pin "84") (pinfunction "84_84") (pintype "passive"))
      (node (ref "MC2") (pin "89") (pinfunction "89_89") (pintype "passive"))
      (node (ref "R23") (pin "2") (pinfunction "2_2") (pintype "passive"))
      (node (ref "R25") (pin "2") (pinfunction "2_2") (pintype "passive"))
      (node (ref "R27") (pin "2") (pinfunction "2_2") (pintype "passive"))
      (node (ref "R28") (pin "1") (pinfunction "1_1") (pintype "passive"))
      (node (ref "TP11") (pin "1") (pinfunction "PIN_1") (pintype "passive"))
      (node (ref "TP12") (pin "1") (pinfunction "PIN_1") (pintype "passive"))
      (node (ref "TP13") (pin "1") (pinfunction "PIN_1") (pintype "passive"))
      (node (ref "TP14") (pin "1") (pinfunction "PIN_1") (pintype "passive"))
      (node (ref "U5") (pin "4") (pinfunction "GND_4") (pintype "power_in"))
      (node (ref "U5") (pin "7") (pinfunction "WP_7") (pintype "input"))
    )
    (net (code "116") (name "MC2_VREF3") (class "Default")
      (node (ref "J2D") (pin "18") (pinfunction "18_18") (pintype "passive"))
      (node (ref "MC2") (pin "114") (pinfunction "114_114") (pintype "passive"))
    )
    (net (code "117") (name "VADJ2") (class "Default")
      (node (ref "J2B") (pin "19") (pinfunction "19_19") (pintype "passive"))
      (node (ref "J2B") (pin "20") (pinfunction "20_20") (pintype "passive"))
      (node (ref "MC2") (pin "59") (pinfunction "59_59") (pintype "passive"))
      (node (ref "MC2") (pin "60") (pinfunction "60_60") (pintype "passive"))
      (node (ref "TP9") (pin "1") (pinfunction "PIN_1") (pintype "passive"))
    )
    (net (code "118") (name "VADJ3") (class "Default")
      (node (ref "J2D") (pin "19") (pinfunction "19_19") (pintype "passive"))
      (node (ref "J2D") (pin "20") (pinfunction "20_20") (pintype "passive"))
      (node (ref "MC2") (pin "119") (pinfunction "119_119") (pintype "passive"))
      (node (ref "MC2") (pin "120") (pinfunction "120_120") (pintype "passive"))
      (node (ref "TP10") (pin "1") (pinfunction "PIN_1") (pintype "passive"))
    )
    (net (code "119") (name "unconnected-(J1-Pad3)") (class "Default")
      (node (ref "J1") (pin "3") (pinfunction "3_3") (pintype "passive+no_connect"))
    )
    (net (code "120") (name "unconnected-(J21-NC-Pad12)") (class "Default")
      (node (ref "J21") (pin "12") (pinfunction "NC_12") (pintype "passive+no_connect"))
    )
    (net (code "121") (name "unconnected-(J21-NC-Pad14)") (class "Default")
      (node (ref "J21") (pin "14") (pinfunction "NC_14") (pintype "passive+no_connect"))
    )
    (net (code "122") (name "unconnected-(MC2-Pad130)") (class "Default")
      (node (ref "MC2") (pin "130") (pinfunction "130_130") (pintype "passive+no_connect"))
    )
    (net (code "123") (name "unconnected-(MC2-Pad132)") (class "Default")
      (node (ref "MC2") (pin "132") (pinfunction "132_132") (pintype "passive+no_connect"))
    )
    (net (code "124") (name "unconnected-(MC2-Pad134)") (class "Default")
      (node (ref "MC2") (pin "134") (pinfunction "134_134") (pintype "passive+no_connect"))
    )
    (net (code "125") (name "unconnected-(MC2-Pad136)") (class "Default")
      (node (ref "MC2") (pin "136") (pinfunction "136_136") (pintype "passive+no_connect"))
    )
    (net (code "126") (name "unconnected-(MC2-Pad137)") (class "Default")
      (node (ref "MC2") (pin "137") (pinfunction "137_137") (pintype "passive+no_connect"))
    )
    (net (code "127") (name "unconnected-(MC2-Pad138)") (class "Default")
      (node (ref "MC2") (pin "138") (pinfunction "138_138") (pintype "passive+no_connect"))
    )
    (net (code "128") (name "unconnected-(MC2-Pad139)") (class "Default")
      (node (ref "MC2") (pin "139") (pinfunction "139_139") (pintype "passive+no_connect"))
    )
    (net (code "129") (name "unconnected-(MC2-Pad140)") (class "Default")
      (node (ref "MC2") (pin "140") (pinfunction "140_140") (pintype "passive+no_connect"))
    )
    (net (code "130") (name "unconnected-(MC2-Pad141)") (class "Default")
      (node (ref "MC2") (pin "141") (pinfunction "141_141") (pintype "passive+no_connect"))
    )
    (net (code "131") (name "unconnected-(MC2-Pad142)") (class "Default")
      (node (ref "MC2") (pin "142") (pinfunction "142_142") (pintype "passive+no_connect"))
    )
    (net (code "132") (name "unconnected-(MC2-Pad143)") (class "Default")
      (node (ref "MC2") (pin "143") (pinfunction "143_143") (pintype "passive+no_connect"))
    )
    (net (code "133") (name "unconnected-(MC2-Pad144)") (class "Default")
      (node (ref "MC2") (pin "144") (pinfunction "144_144") (pintype "passive+no_connect"))
    )
    (net (code "134") (name "unconnected-(MC2-Pad145)") (class "Default")
      (node (ref "MC2") (pin "145") (pinfunction "145_145") (pintype "passive+no_connect"))
    )
    (net (code "135") (name "unconnected-(MC2-Pad146)") (class "Default")
      (node (ref "MC2") (pin "146") (pinfunction "146_146") (pintype "passive+no_connect"))
    )
    (net (code "136") (name "unconnected-(MC2-Pad150)") (class "Default")
      (node (ref "MC2") (pin "150") (pinfunction "150_150") (pintype "passive+no_connect"))
    )
    (net (code "137") (name "unconnected-(MC2-Pad151)") (class "Default")
      (node (ref "MC2") (pin "151") (pinfunction "151_151") (pintype "passive+no_connect"))
    )
    (net (code "138") (name "unconnected-(MC2-Pad152)") (class "Default")
      (node (ref "MC2") (pin "152") (pinfunction "152_152") (pintype "passive+no_connect"))
    )
    (net (code "139") (name "unconnected-(MC2-Pad153)") (class "Default")
      (node (ref "MC2") (pin "153") (pinfunction "153_153") (pintype "passive+no_connect"))
    )
    (net (code "140") (name "unconnected-(MC2-Pad154)") (class "Default")
      (node (ref "MC2") (pin "154") (pinfunction "154_154") (pintype "passive+no_connect"))
    )
    (net (code "141") (name "unconnected-(MC2-Pad155)") (class "Default")
      (node (ref "MC2") (pin "155") (pinfunction "155_155") (pintype "passive+no_connect"))
    )
    (net (code "142") (name "unconnected-(MC2-Pad156)") (class "Default")
      (node (ref "MC2") (pin "156") (pinfunction "156_156") (pintype "passive+no_connect"))
    )
    (net (code "143") (name "unconnected-(MC2-Pad157)") (class "Default")
      (node (ref "MC2") (pin "157") (pinfunction "157_157") (pintype "passive+no_connect"))
    )
    (net (code "144") (name "unconnected-(MC2-Pad158)") (class "Default")
      (node (ref "MC2") (pin "158") (pinfunction "158_158") (pintype "passive+no_connect"))
    )
    (net (code "145") (name "unconnected-(MC2-Pad159)") (class "Default")
      (node (ref "MC2") (pin "159") (pinfunction "159_159") (pintype "passive+no_connect"))
    )
    (net (code "146") (name "unconnected-(MC2-Pad160)") (class "Default")
      (node (ref "MC2") (pin "160") (pinfunction "160_160") (pintype "passive+no_connect"))
    )
    (net (code "147") (name "unconnected-(MC2-Pad161)") (class "Default")
      (node (ref "MC2") (pin "161") (pinfunction "161_161") (pintype "passive+no_connect"))
    )
    (net (code "148") (name "unconnected-(MC2-Pad162)") (class "Default")
      (node (ref "MC2") (pin "162") (pinfunction "162_162") (pintype "passive+no_connect"))
    )
    (net (code "149") (name "unconnected-(MC2-Pad163)") (class "Default")
      (node (ref "MC2") (pin "163") (pinfunction "163_163") (pintype "passive+no_connect"))
    )
    (net (code "150") (name "unconnected-(MC2-Pad164)") (class "Default")
      (node (ref "MC2") (pin "164") (pinfunction "164_164") (pintype "passive+no_connect"))
    )
    (net (code "151") (name "unconnected-(MC2-Pad165)") (class "Default")
      (node (ref "MC2") (pin "165") (pinfunction "165_165") (pintype "passive+no_connect"))
    )
    (net (code "152") (name "unconnected-(MC2-Pad166)") (class "Default")
      (node (ref "MC2") (pin "166") (pinfunction "166_166") (pintype "passive+no_connect"))
    )
    (net (code "153") (name "unconnected-(MC2-Pad167)") (class "Default")
      (node (ref "MC2") (pin "167") (pinfunction "167_167") (pintype "passive+no_connect"))
    )
    (net (code "154") (name "unconnected-(MC2-Pad168)") (class "Default")
      (node (ref "MC2") (pin "168") (pinfunction "168_168") (pintype "passive+no_connect"))
    )
    (net (code "155") (name "unconnected-(MC2-Pad169)") (class "Default")
      (node (ref "MC2") (pin "169") (pinfunction "169_169") (pintype "passive+no_connect"))
    )
    (net (code "156") (name "unconnected-(MC2-Pad171)") (class "Default")
      (node (ref "MC2") (pin "171") (pinfunction "171_171") (pintype "passive+no_connect"))
    )
    (net (code "157") (name "unconnected-(MC2-Pad173)") (class "Default")
      (node (ref "MC2") (pin "173") (pinfunction "173_173") (pintype "passive+no_connect"))
    )
  )
)
